# main.net
KiCad netlist of a schematic drawn in EAGLE
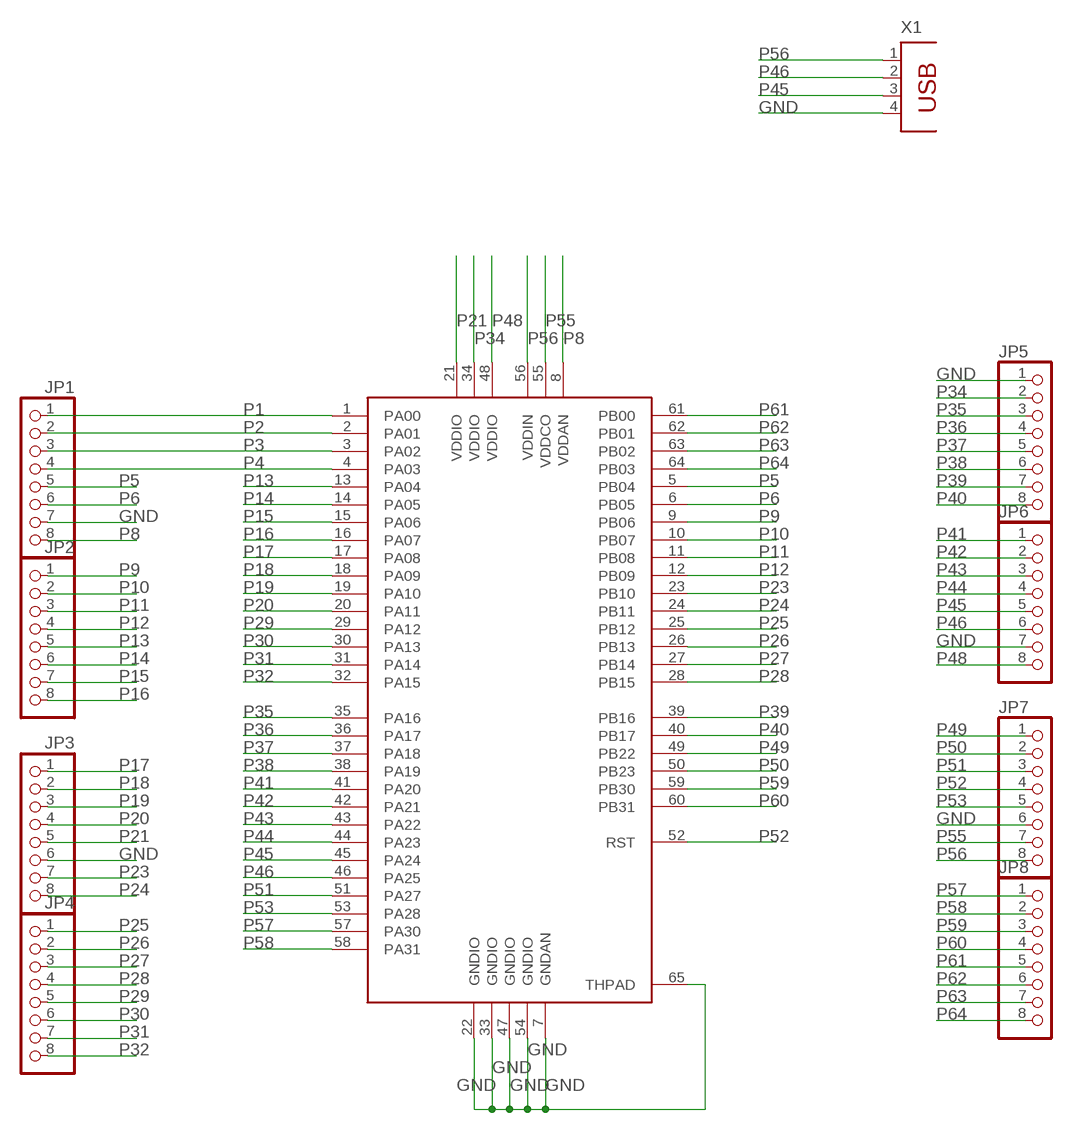
[diagram p0: schematic, sheet 1]

(export (version "E")
  (design (tool "Eeschema 10.0.6"))
  (components
    (comp (ref "JP1")
      (value "PINHD-1X8CLEANBIG")
      (footprint "eagle-import:1X08-CLEANBIG")
      (libsource (lib "eagle-import") (part "PINHD-1X8CLEANBIG"))
    )
    (comp (ref "JP2")
      (value "PINHD-1X8CLEANBIG")
      (footprint "eagle-import:1X08-CLEANBIG")
      (libsource (lib "eagle-import") (part "PINHD-1X8CLEANBIG"))
    )
    (comp (ref "JP3")
      (value "PINHD-1X8CLEANBIG")
      (footprint "eagle-import:1X08-CLEANBIG")
      (libsource (lib "eagle-import") (part "PINHD-1X8CLEANBIG"))
    )
    (comp (ref "JP4")
      (value "PINHD-1X8CLEANBIG")
      (footprint "eagle-import:1X08-CLEANBIG")
      (libsource (lib "eagle-import") (part "PINHD-1X8CLEANBIG"))
    )
    (comp (ref "JP5")
      (value "PINHD-1X8CLEANBIG")
      (footprint "eagle-import:1X08-CLEANBIG")
      (libsource (lib "eagle-import") (part "PINHD-1X8CLEANBIG"))
    )
    (comp (ref "JP6")
      (value "PINHD-1X8CLEANBIG")
      (footprint "eagle-import:1X08-CLEANBIG")
      (libsource (lib "eagle-import") (part "PINHD-1X8CLEANBIG"))
    )
    (comp (ref "JP7")
      (value "PINHD-1X8CLEANBIG")
      (footprint "eagle-import:1X08-CLEANBIG")
      (libsource (lib "eagle-import") (part "PINHD-1X8CLEANBIG"))
    )
    (comp (ref "JP8")
      (value "PINHD-1X8CLEANBIG")
      (footprint "eagle-import:1X08-CLEANBIG")
      (libsource (lib "eagle-import") (part "PINHD-1X8CLEANBIG"))
    )
    (comp (ref "U$1")
      (value "ATSAMD21J18AQFN64")
      (footprint "eagle-import:QFN50P900X900X100-65T535")
      (libsource (lib "eagle-import") (part "ATSAMD21J18AQFN64"))
    )
    (comp (ref "X1")
      (value "PN61729")
      (footprint "eagle-import:PN61729")
      (libsource (lib "eagle-import") (part "PN61729"))
    )
  )
  (nets
    (net (code "1") (name "/GND") (class "Default")
      (node (ref "JP1") (pin "7") (pinfunction "7_7") (pintype "passive"))
      (node (ref "JP3") (pin "6") (pinfunction "6_6") (pintype "passive"))
      (node (ref "JP5") (pin "1") (pinfunction "1_1") (pintype "passive"))
      (node (ref "JP6") (pin "7") (pinfunction "7_7") (pintype "passive"))
      (node (ref "JP7") (pin "6") (pinfunction "6_6") (pintype "passive"))
      (node (ref "U$1") (pin "22") (pinfunction "GNDIO_22") (pintype "bidirectional"))
      (node (ref "U$1") (pin "33") (pinfunction "GNDIO_33") (pintype "bidirectional"))
      (node (ref "U$1") (pin "47") (pinfunction "GNDIO_47") (pintype "bidirectional"))
      (node (ref "U$1") (pin "54") (pinfunction "GNDIO_54") (pintype "bidirectional"))
      (node (ref "U$1") (pin "65") (pinfunction "THPAD_65") (pintype "bidirectional"))
      (node (ref "U$1") (pin "7") (pinfunction "GNDAN_7") (pintype "bidirectional"))
      (node (ref "X1") (pin "4") (pinfunction "4_4") (pintype "passive"))
    )
    (net (code "2") (name "/P1") (class "Default")
      (node (ref "JP1") (pin "1") (pinfunction "1_1") (pintype "passive"))
      (node (ref "U$1") (pin "1") (pinfunction "PA00_1") (pintype "bidirectional"))
    )
    (net (code "3") (name "/P2") (class "Default")
      (node (ref "JP1") (pin "2") (pinfunction "2_2") (pintype "passive"))
      (node (ref "U$1") (pin "2") (pinfunction "PA01_2") (pintype "bidirectional"))
    )
    (net (code "4") (name "/P3") (class "Default")
      (node (ref "JP1") (pin "3") (pinfunction "3_3") (pintype "passive"))
      (node (ref "U$1") (pin "3") (pinfunction "PA02_3") (pintype "bidirectional"))
    )
    (net (code "5") (name "/P4") (class "Default")
      (node (ref "JP1") (pin "4") (pinfunction "4_4") (pintype "passive"))
      (node (ref "U$1") (pin "4") (pinfunction "PA03_4") (pintype "bidirectional"))
    )
    (net (code "6") (name "/P5") (class "Default")
      (node (ref "JP1") (pin "5") (pinfunction "5_5") (pintype "passive"))
      (node (ref "U$1") (pin "5") (pinfunction "PB04_5") (pintype "bidirectional"))
    )
    (net (code "7") (name "/P6") (class "Default")
      (node (ref "JP1") (pin "6") (pinfunction "6_6") (pintype "passive"))
      (node (ref "U$1") (pin "6") (pinfunction "PB05_6") (pintype "bidirectional"))
    )
    (net (code "8") (name "/P8") (class "Default")
      (node (ref "JP1") (pin "8") (pinfunction "8_8") (pintype "passive"))
      (node (ref "U$1") (pin "8") (pinfunction "VDDAN_8") (pintype "bidirectional"))
    )
    (net (code "9") (name "/P9") (class "Default")
      (node (ref "JP2") (pin "1") (pinfunction "1_1") (pintype "passive"))
      (node (ref "U$1") (pin "9") (pinfunction "PB06_9") (pintype "bidirectional"))
    )
    (net (code "10") (name "/P10") (class "Default")
      (node (ref "JP2") (pin "2") (pinfunction "2_2") (pintype "passive"))
      (node (ref "U$1") (pin "10") (pinfunction "PB07_10") (pintype "bidirectional"))
    )
    (net (code "11") (name "/P11") (class "Default")
      (node (ref "JP2") (pin "3") (pinfunction "3_3") (pintype "passive"))
      (node (ref "U$1") (pin "11") (pinfunction "PB08_11") (pintype "bidirectional"))
    )
    (net (code "12") (name "/P12") (class "Default")
      (node (ref "JP2") (pin "4") (pinfunction "4_4") (pintype "passive"))
      (node (ref "U$1") (pin "12") (pinfunction "PB09_12") (pintype "bidirectional"))
    )
    (net (code "13") (name "/P13") (class "Default")
      (node (ref "JP2") (pin "5") (pinfunction "5_5") (pintype "passive"))
      (node (ref "U$1") (pin "13") (pinfunction "PA04_13") (pintype "bidirectional"))
    )
    (net (code "14") (name "/P14") (class "Default")
      (node (ref "JP2") (pin "6") (pinfunction "6_6") (pintype "passive"))
      (node (ref "U$1") (pin "14") (pinfunction "PA05_14") (pintype "bidirectional"))
    )
    (net (code "15") (name "/P15") (class "Default")
      (node (ref "JP2") (pin "7") (pinfunction "7_7") (pintype "passive"))
      (node (ref "U$1") (pin "15") (pinfunction "PA06_15") (pintype "bidirectional"))
    )
    (net (code "16") (name "/P16") (class "Default")
      (node (ref "JP2") (pin "8") (pinfunction "8_8") (pintype "passive"))
      (node (ref "U$1") (pin "16") (pinfunction "PA07_16") (pintype "bidirectional"))
    )
    (net (code "17") (name "/P17") (class "Default")
      (node (ref "JP3") (pin "1") (pinfunction "1_1") (pintype "passive"))
      (node (ref "U$1") (pin "17") (pinfunction "PA08_17") (pintype "bidirectional"))
    )
    (net (code "18") (name "/P18") (class "Default")
      (node (ref "JP3") (pin "2") (pinfunction "2_2") (pintype "passive"))
      (node (ref "U$1") (pin "18") (pinfunction "PA09_18") (pintype "bidirectional"))
    )
    (net (code "19") (name "/P19") (class "Default")
      (node (ref "JP3") (pin "3") (pinfunction "3_3") (pintype "passive"))
      (node (ref "U$1") (pin "19") (pinfunction "PA10_19") (pintype "bidirectional"))
    )
    (net (code "20") (name "/P20") (class "Default")
      (node (ref "JP3") (pin "4") (pinfunction "4_4") (pintype "passive"))
      (node (ref "U$1") (pin "20") (pinfunction "PA11_20") (pintype "bidirectional"))
    )
    (net (code "21") (name "/P21") (class "Default")
      (node (ref "JP3") (pin "5") (pinfunction "5_5") (pintype "passive"))
      (node (ref "U$1") (pin "21") (pinfunction "VDDIO_21") (pintype "bidirectional"))
    )
    (net (code "22") (name "/P23") (class "Default")
      (node (ref "JP3") (pin "7") (pinfunction "7_7") (pintype "passive"))
      (node (ref "U$1") (pin "23") (pinfunction "PB10_23") (pintype "bidirectional"))
    )
    (net (code "23") (name "/P24") (class "Default")
      (node (ref "JP3") (pin "8") (pinfunction "8_8") (pintype "passive"))
      (node (ref "U$1") (pin "24") (pinfunction "PB11_24") (pintype "bidirectional"))
    )
    (net (code "24") (name "/P25") (class "Default")
      (node (ref "JP4") (pin "1") (pinfunction "1_1") (pintype "passive"))
      (node (ref "U$1") (pin "25") (pinfunction "PB12_25") (pintype "bidirectional"))
    )
    (net (code "25") (name "/P26") (class "Default")
      (node (ref "JP4") (pin "2") (pinfunction "2_2") (pintype "passive"))
      (node (ref "U$1") (pin "26") (pinfunction "PB13_26") (pintype "bidirectional"))
    )
    (net (code "26") (name "/P27") (class "Default")
      (node (ref "JP4") (pin "3") (pinfunction "3_3") (pintype "passive"))
      (node (ref "U$1") (pin "27") (pinfunction "PB14_27") (pintype "bidirectional"))
    )
    (net (code "27") (name "/P28") (class "Default")
      (node (ref "JP4") (pin "4") (pinfunction "4_4") (pintype "passive"))
      (node (ref "U$1") (pin "28") (pinfunction "PB15_28") (pintype "bidirectional"))
    )
    (net (code "28") (name "/P29") (class "Default")
      (node (ref "JP4") (pin "5") (pinfunction "5_5") (pintype "passive"))
      (node (ref "U$1") (pin "29") (pinfunction "PA12_29") (pintype "bidirectional"))
    )
    (net (code "29") (name "/P30") (class "Default")
      (node (ref "JP4") (pin "6") (pinfunction "6_6") (pintype "passive"))
      (node (ref "U$1") (pin "30") (pinfunction "PA13_30") (pintype "bidirectional"))
    )
    (net (code "30") (name "/P31") (class "Default")
      (node (ref "JP4") (pin "7") (pinfunction "7_7") (pintype "passive"))
      (node (ref "U$1") (pin "31") (pinfunction "PA14_31") (pintype "bidirectional"))
    )
    (net (code "31") (name "/P32") (class "Default")
      (node (ref "JP4") (pin "8") (pinfunction "8_8") (pintype "passive"))
      (node (ref "U$1") (pin "32") (pinfunction "PA15_32") (pintype "bidirectional"))
    )
    (net (code "32") (name "/P34") (class "Default")
      (node (ref "JP5") (pin "2") (pinfunction "2_2") (pintype "passive"))
      (node (ref "U$1") (pin "34") (pinfunction "VDDIO_34") (pintype "bidirectional"))
    )
    (net (code "33") (name "/P35") (class "Default")
      (node (ref "JP5") (pin "3") (pinfunction "3_3") (pintype "passive"))
      (node (ref "U$1") (pin "35") (pinfunction "PA16_35") (pintype "bidirectional"))
    )
    (net (code "34") (name "/P36") (class "Default")
      (node (ref "JP5") (pin "4") (pinfunction "4_4") (pintype "passive"))
      (node (ref "U$1") (pin "36") (pinfunction "PA17_36") (pintype "bidirectional"))
    )
    (net (code "35") (name "/P37") (class "Default")
      (node (ref "JP5") (pin "5") (pinfunction "5_5") (pintype "passive"))
      (node (ref "U$1") (pin "37") (pinfunction "PA18_37") (pintype "bidirectional"))
    )
    (net (code "36") (name "/P38") (class "Default")
      (node (ref "JP5") (pin "6") (pinfunction "6_6") (pintype "passive"))
      (node (ref "U$1") (pin "38") (pinfunction "PA19_38") (pintype "bidirectional"))
    )
    (net (code "37") (name "/P39") (class "Default")
      (node (ref "JP5") (pin "7") (pinfunction "7_7") (pintype "passive"))
      (node (ref "U$1") (pin "39") (pinfunction "PB16_39") (pintype "bidirectional"))
    )
    (net (code "38") (name "/P40") (class "Default")
      (node (ref "JP5") (pin "8") (pinfunction "8_8") (pintype "passive"))
      (node (ref "U$1") (pin "40") (pinfunction "PB17_40") (pintype "bidirectional"))
    )
    (net (code "39") (name "/P41") (class "Default")
      (node (ref "JP6") (pin "1") (pinfunction "1_1") (pintype "passive"))
      (node (ref "U$1") (pin "41") (pinfunction "PA20_41") (pintype "bidirectional"))
    )
    (net (code "40") (name "/P42") (class "Default")
      (node (ref "JP6") (pin "2") (pinfunction "2_2") (pintype "passive"))
      (node (ref "U$1") (pin "42") (pinfunction "PA21_42") (pintype "bidirectional"))
    )
    (net (code "41") (name "/P43") (class "Default")
      (node (ref "JP6") (pin "3") (pinfunction "3_3") (pintype "passive"))
      (node (ref "U$1") (pin "43") (pinfunction "PA22_43") (pintype "bidirectional"))
    )
    (net (code "42") (name "/P44") (class "Default")
      (node (ref "JP6") (pin "4") (pinfunction "4_4") (pintype "passive"))
      (node (ref "U$1") (pin "44") (pinfunction "PA23_44") (pintype "bidirectional"))
    )
    (net (code "43") (name "/P45") (class "Default")
      (node (ref "JP6") (pin "5") (pinfunction "5_5") (pintype "passive"))
      (node (ref "U$1") (pin "45") (pinfunction "PA24_45") (pintype "bidirectional"))
      (node (ref "X1") (pin "3") (pinfunction "3_3") (pintype "passive"))
    )
    (net (code "44") (name "/P46") (class "Default")
      (node (ref "JP6") (pin "6") (pinfunction "6_6") (pintype "passive"))
      (node (ref "U$1") (pin "46") (pinfunction "PA25_46") (pintype "bidirectional"))
      (node (ref "X1") (pin "2") (pinfunction "2_2") (pintype "passive"))
    )
    (net (code "45") (name "/P48") (class "Default")
      (node (ref "JP6") (pin "8") (pinfunction "8_8") (pintype "passive"))
      (node (ref "U$1") (pin "48") (pinfunction "VDDIO_48") (pintype "bidirectional"))
    )
    (net (code "46") (name "/P49") (class "Default")
      (node (ref "JP7") (pin "1") (pinfunction "1_1") (pintype "passive"))
      (node (ref "U$1") (pin "49") (pinfunction "PB22_49") (pintype "bidirectional"))
    )
    (net (code "47") (name "/P50") (class "Default")
      (node (ref "JP7") (pin "2") (pinfunction "2_2") (pintype "passive"))
      (node (ref "U$1") (pin "50") (pinfunction "PB23_50") (pintype "bidirectional"))
    )
    (net (code "48") (name "/P51") (class "Default")
      (node (ref "JP7") (pin "3") (pinfunction "3_3") (pintype "passive"))
      (node (ref "U$1") (pin "51") (pinfunction "PA27_51") (pintype "bidirectional"))
    )
    (net (code "49") (name "/P52") (class "Default")
      (node (ref "JP7") (pin "4") (pinfunction "4_4") (pintype "passive"))
      (node (ref "U$1") (pin "52") (pinfunction "RST_52") (pintype "bidirectional"))
    )
    (net (code "50") (name "/P53") (class "Default")
      (node (ref "JP7") (pin "5") (pinfunction "5_5") (pintype "passive"))
      (node (ref "U$1") (pin "53") (pinfunction "PA28_53") (pintype "bidirectional"))
    )
    (net (code "51") (name "/P55") (class "Default")
      (node (ref "JP7") (pin "7") (pinfunction "7_7") (pintype "passive"))
      (node (ref "U$1") (pin "55") (pinfunction "VDDCO_55") (pintype "bidirectional"))
    )
    (net (code "52") (name "/P56") (class "Default")
      (node (ref "JP7") (pin "8") (pinfunction "8_8") (pintype "passive"))
      (node (ref "U$1") (pin "56") (pinfunction "VDDIN_56") (pintype "bidirectional"))
      (node (ref "X1") (pin "1") (pinfunction "1_1") (pintype "passive"))
    )
    (net (code "53") (name "/P57") (class "Default")
      (node (ref "JP8") (pin "1") (pinfunction "1_1") (pintype "passive"))
      (node (ref "U$1") (pin "57") (pinfunction "PA30_57") (pintype "bidirectional"))
    )
    (net (code "54") (name "/P58") (class "Default")
      (node (ref "JP8") (pin "2") (pinfunction "2_2") (pintype "passive"))
      (node (ref "U$1") (pin "58") (pinfunction "PA31_58") (pintype "bidirectional"))
    )
    (net (code "55") (name "/P59") (class "Default")
      (node (ref "JP8") (pin "3") (pinfunction "3_3") (pintype "passive"))
      (node (ref "U$1") (pin "59") (pinfunction "PB30_59") (pintype "bidirectional"))
    )
    (net (code "56") (name "/P60") (class "Default")
      (node (ref "JP8") (pin "4") (pinfunction "4_4") (pintype "passive"))
      (node (ref "U$1") (pin "60") (pinfunction "PB31_60") (pintype "bidirectional"))
    )
    (net (code "57") (name "/P61") (class "Default")
      (node (ref "JP8") (pin "5") (pinfunction "5_5") (pintype "passive"))
      (node (ref "U$1") (pin "61") (pinfunction "PB00_61") (pintype "bidirectional"))
    )
    (net (code "58") (name "/P62") (class "Default")
      (node (ref "JP8") (pin "6") (pinfunction "6_6") (pintype "passive"))
      (node (ref "U$1") (pin "62") (pinfunction "PB01_62") (pintype "bidirectional"))
    )
    (net (code "59") (name "/P63") (class "Default")
      (node (ref "JP8") (pin "7") (pinfunction "7_7") (pintype "passive"))
      (node (ref "U$1") (pin "63") (pinfunction "PB02_63") (pintype "bidirectional"))
    )
    (net (code "60") (name "/P64") (class "Default")
      (node (ref "JP8") (pin "8") (pinfunction "8_8") (pintype "passive"))
      (node (ref "U$1") (pin "64") (pinfunction "PB03_64") (pintype "bidirectional"))
    )
  )
)
